# pcb.net
KiCad netlist of a schematic drawn in EasyEDA
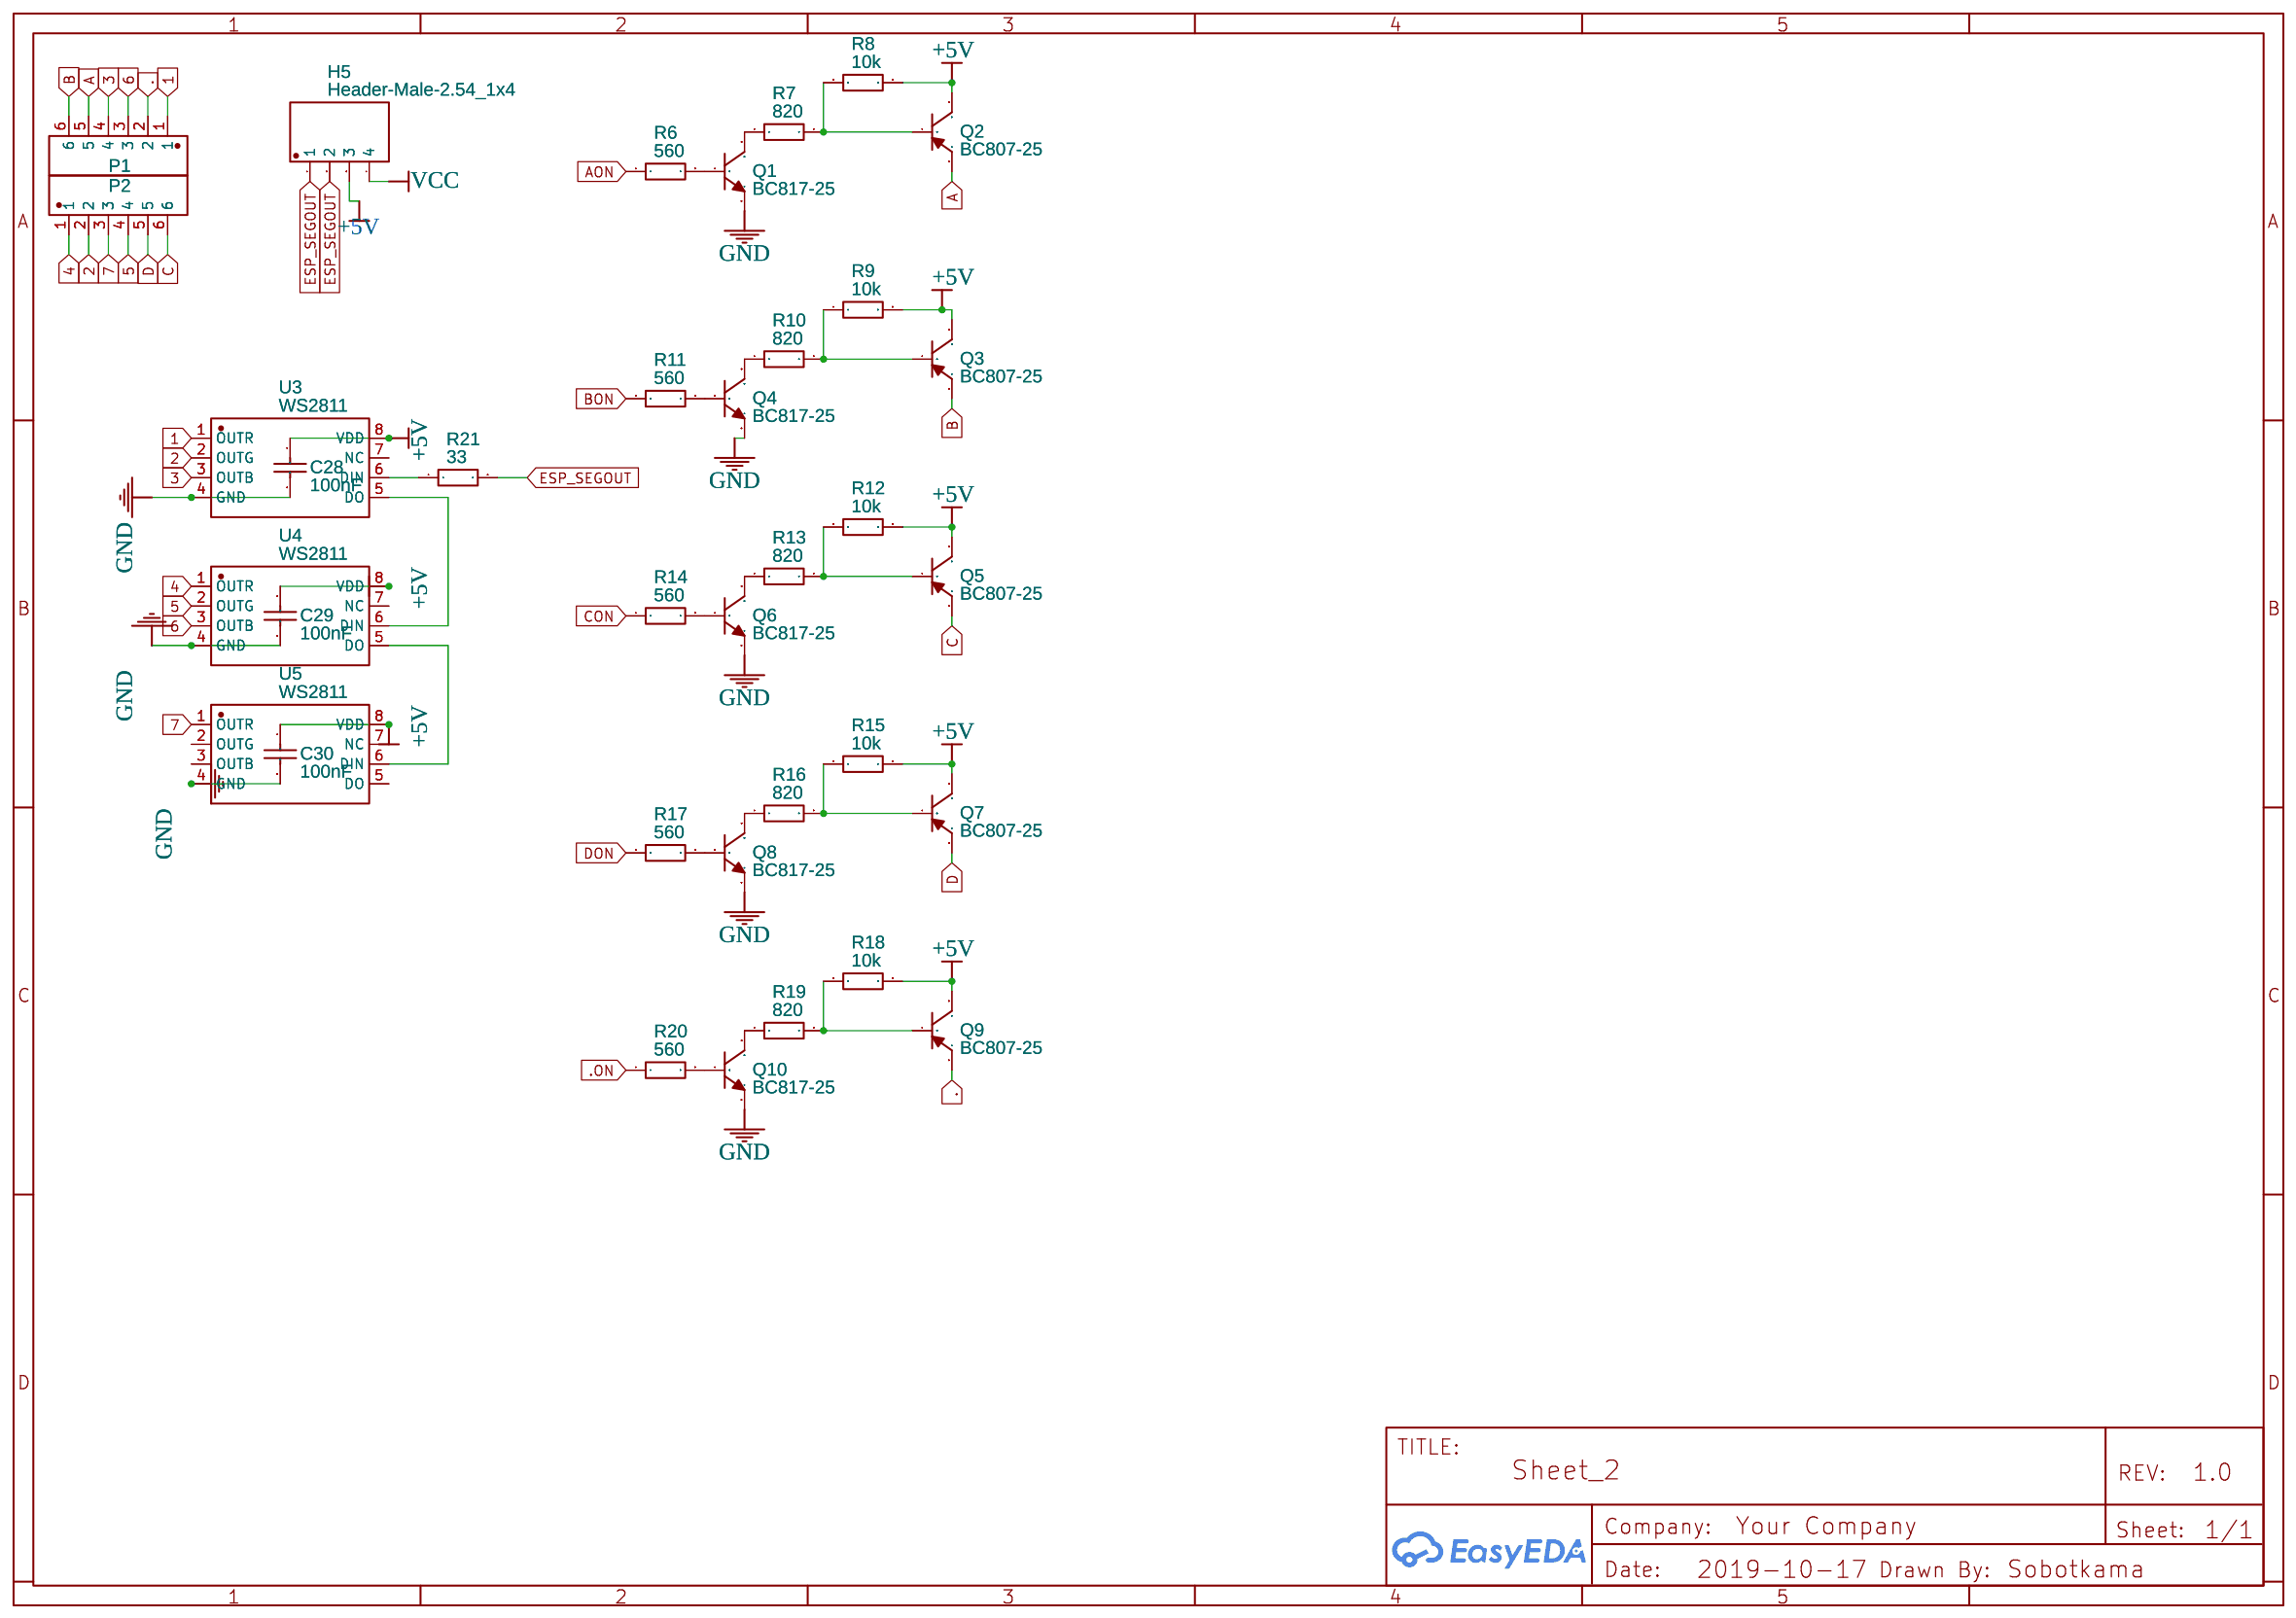
[diagram p0: Sheet_2]
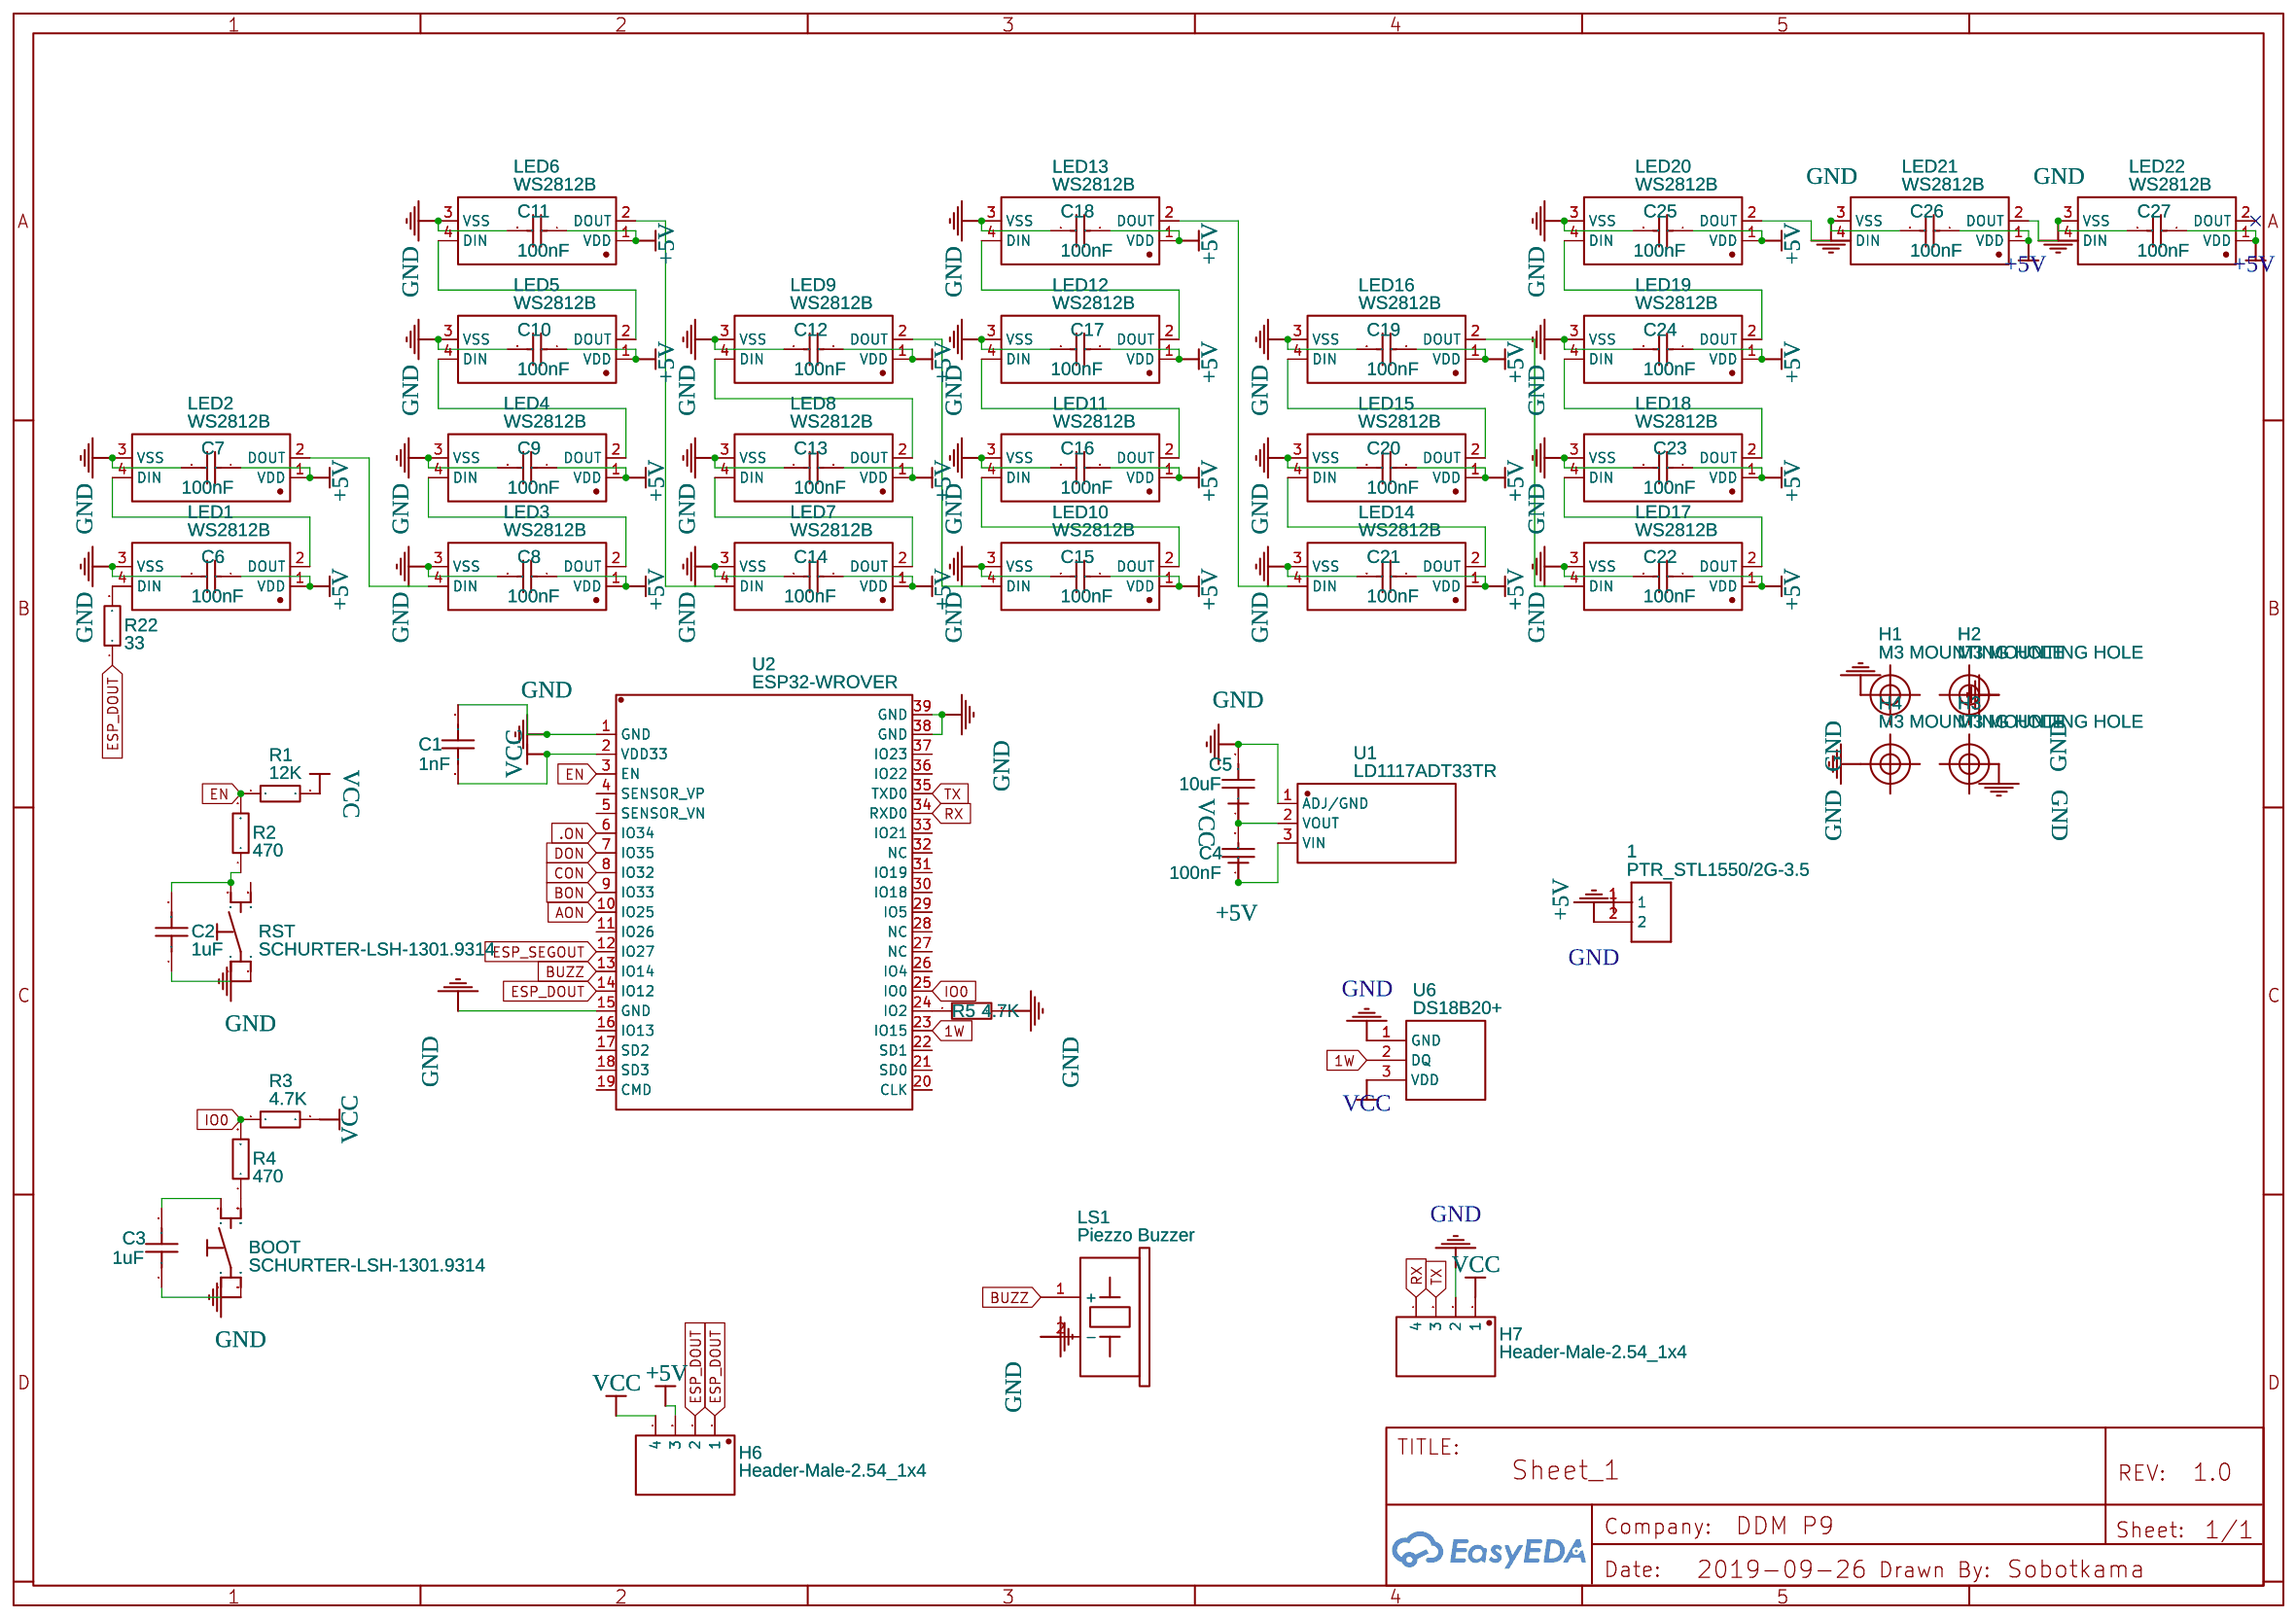
[diagram p1: Sheet_1]
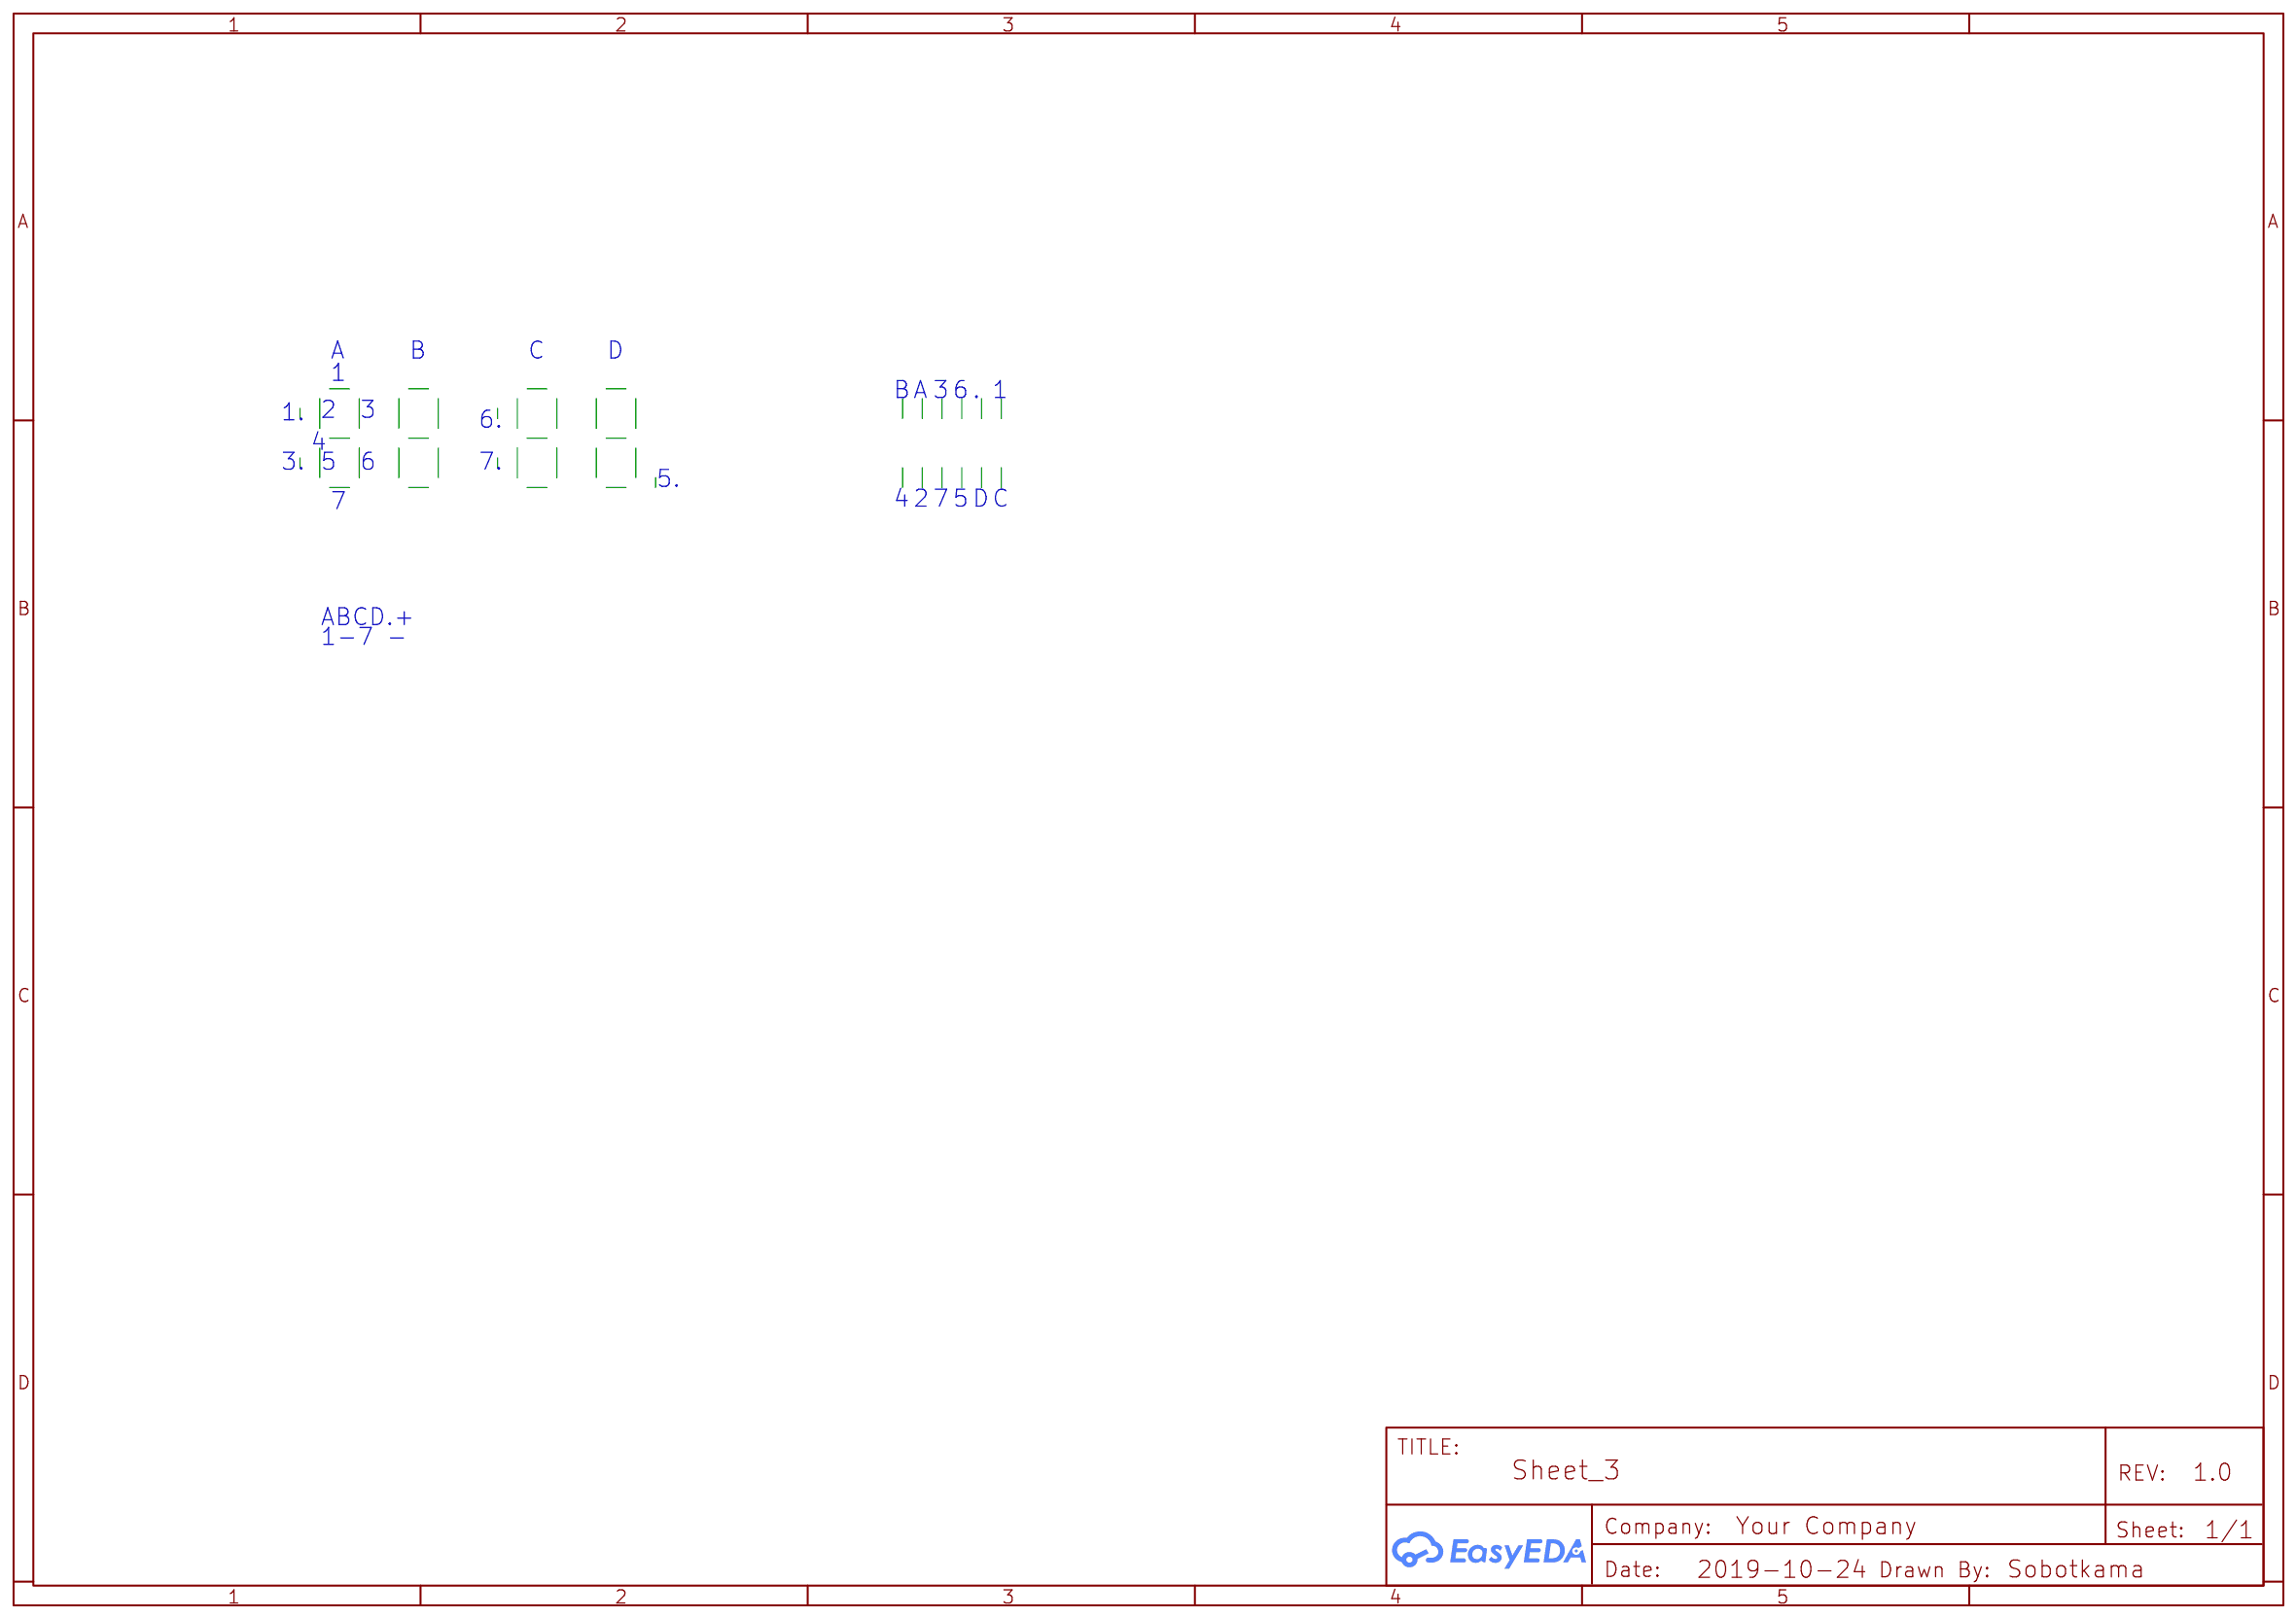
[diagram p2: DISPLAY_MAP]

(export (version "E")
  (design (tool "Eeschema 10.0.6"))
  (components
    (comp (ref "C28")
      (value "100nF")
      (fields
        (field (name "BOM_Manufacturer Part") "CL31B104KCFNNNE")
        (field (name "BOM_Supplier Part") "C1945")
      )
      (libsource (lib "") (part "CL31B104KCFNNNE"))
    )
    (comp (ref "C29")
      (value "100nF")
      (fields
        (field (name "BOM_Manufacturer Part") "CL31B104KCFNNNE")
        (field (name "BOM_Supplier Part") "C1945")
      )
      (libsource (lib "") (part "CL31B104KCFNNNE"))
    )
    (comp (ref "C30")
      (value "100nF")
      (fields
        (field (name "BOM_Manufacturer Part") "CL31B104KCFNNNE")
        (field (name "BOM_Supplier Part") "C1945")
      )
      (libsource (lib "") (part "CL31B104KCFNNNE"))
    )
    (comp (ref "H5")
      (value "Header-Male-2.54_1x4")
      (fields
        (field (name "BOM_Manufacturer Part") "210S-1*4P L=11.6MMGold-plated black")
        (field (name "BOM_Supplier Part") "C124378")
      )
      (libsource (lib "") (part "Header-Male-2.54_1x4"))
    )
    (comp (ref "P1")
      (value "Header-Female-2.54_1x6")
      (fields
        (field (name "BOM_Manufacturer Part") "Female header 1*6p")
        (field (name "BOM_Supplier Part") "C40877")
      )
      (libsource (lib "") (part "Unknown_53_72"))
    )
    (comp (ref "P2")
      (value "Header-Female-2.54_1x6")
      (fields
        (field (name "BOM_Manufacturer Part") "Female header 1*6p")
        (field (name "BOM_Supplier Part") "C40877")
      )
      (libsource (lib "") (part "Unknown_53_92"))
    )
    (comp (ref "Q1")
      (value "BC817-25")
      (fields (field (name "BOM_Supplier Part") "C8588"))
      (libsource (lib "") (part "Unknown_360_80"))
    )
    (comp (ref "Q2")
      (value "BC807-25")
      (fields (field (name "BOM_Supplier Part") "C181150"))
      (libsource (lib "") (part "Unknown_465_60"))
    )
    (comp (ref "Q3")
      (value "BC807-25")
      (fields (field (name "BOM_Supplier Part") "C181150"))
      (libsource (lib "") (part "Unknown_465_175"))
    )
    (comp (ref "Q4")
      (value "BC817-25")
      (fields (field (name "BOM_Supplier Part") "C8588"))
      (libsource (lib "") (part "Unknown_360_195"))
    )
    (comp (ref "Q5")
      (value "BC807-25")
      (fields (field (name "BOM_Supplier Part") "C181150"))
      (libsource (lib "") (part "Unknown_465_285"))
    )
    (comp (ref "Q6")
      (value "BC817-25")
      (fields (field (name "BOM_Supplier Part") "C8588"))
      (libsource (lib "") (part "Unknown_360_305"))
    )
    (comp (ref "Q7")
      (value "BC807-25")
      (fields (field (name "BOM_Supplier Part") "C181150"))
      (libsource (lib "") (part "Unknown_465_405"))
    )
    (comp (ref "Q8")
      (value "BC817-25")
      (fields (field (name "BOM_Supplier Part") "C8588"))
      (libsource (lib "") (part "Unknown_360_425"))
    )
    (comp (ref "Q9")
      (value "BC807-25")
      (fields (field (name "BOM_Supplier Part") "C181150"))
      (libsource (lib "") (part "Unknown_465_515"))
    )
    (comp (ref "Q10")
      (value "BC817-25")
      (fields (field (name "BOM_Supplier Part") "C8588"))
      (libsource (lib "") (part "Unknown_360_535"))
    )
    (comp (ref "R6")
      (value "560")
      (fields
        (field (name "BOM_Manufacturer Part") "RMC12065601%N")
        (field (name "BOM_Supplier Part") "C269625")
      )
      (libsource (lib "") (part "RMC12065601%N"))
    )
    (comp (ref "R7")
      (value "820")
      (fields
        (field (name "BOM_Manufacturer Part") "RC1206JR-071KL")
        (field (name "BOM_Supplier Part") "C112223")
      )
      (libsource (lib "") (part "RC1206JR-071KL"))
    )
    (comp (ref "R8")
      (value "10k")
      (fields
        (field (name "BOM_Manufacturer Part") "AECR1206F4K70K9")
        (field (name "BOM_Supplier Part") "C352065")
      )
      (libsource (lib "") (part "AECR1206F4K70K9"))
    )
    (comp (ref "R9")
      (value "10k")
      (fields
        (field (name "BOM_Manufacturer Part") "AECR1206F4K70K9")
        (field (name "BOM_Supplier Part") "C352065")
      )
      (libsource (lib "") (part "AECR1206F4K70K9"))
    )
    (comp (ref "R10")
      (value "820")
      (fields
        (field (name "BOM_Manufacturer Part") "RC1206JR-071KL")
        (field (name "BOM_Supplier Part") "C112223")
      )
      (libsource (lib "") (part "RC1206JR-071KL"))
    )
    (comp (ref "R11")
      (value "560")
      (fields
        (field (name "BOM_Manufacturer Part") "RMC12065601%N")
        (field (name "BOM_Supplier Part") "C269625")
      )
      (libsource (lib "") (part "RMC12065601%N"))
    )
    (comp (ref "R12")
      (value "10k")
      (fields
        (field (name "BOM_Manufacturer Part") "AECR1206F4K70K9")
        (field (name "BOM_Supplier Part") "C352065")
      )
      (libsource (lib "") (part "AECR1206F4K70K9"))
    )
    (comp (ref "R13")
      (value "820")
      (fields
        (field (name "BOM_Manufacturer Part") "RC1206JR-071KL")
        (field (name "BOM_Supplier Part") "C112223")
      )
      (libsource (lib "") (part "RC1206JR-071KL"))
    )
    (comp (ref "R14")
      (value "560")
      (fields
        (field (name "BOM_Manufacturer Part") "RMC12065601%N")
        (field (name "BOM_Supplier Part") "C269625")
      )
      (libsource (lib "") (part "RMC12065601%N"))
    )
    (comp (ref "R15")
      (value "10k")
      (fields
        (field (name "BOM_Manufacturer Part") "AECR1206F4K70K9")
        (field (name "BOM_Supplier Part") "C352065")
      )
      (libsource (lib "") (part "AECR1206F4K70K9"))
    )
    (comp (ref "R16")
      (value "820")
      (fields
        (field (name "BOM_Manufacturer Part") "RC1206JR-071KL")
        (field (name "BOM_Supplier Part") "C112223")
      )
      (libsource (lib "") (part "RC1206JR-071KL"))
    )
    (comp (ref "R17")
      (value "560")
      (fields
        (field (name "BOM_Manufacturer Part") "RMC12065601%N")
        (field (name "BOM_Supplier Part") "C269625")
      )
      (libsource (lib "") (part "RMC12065601%N"))
    )
    (comp (ref "R18")
      (value "10k")
      (fields
        (field (name "BOM_Manufacturer Part") "AECR1206F4K70K9")
        (field (name "BOM_Supplier Part") "C352065")
      )
      (libsource (lib "") (part "AECR1206F4K70K9"))
    )
    (comp (ref "R19")
      (value "820")
      (fields
        (field (name "BOM_Manufacturer Part") "RC1206JR-071KL")
        (field (name "BOM_Supplier Part") "C112223")
      )
      (libsource (lib "") (part "RC1206JR-071KL"))
    )
    (comp (ref "R20")
      (value "560")
      (fields
        (field (name "BOM_Manufacturer Part") "RMC12065601%N")
        (field (name "BOM_Supplier Part") "C269625")
      )
      (libsource (lib "") (part "RMC12065601%N"))
    )
    (comp (ref "R21")
      (value "33")
      (fields
        (field (name "BOM_Manufacturer Part") "RT1206FRD0720RL")
        (field (name "BOM_Supplier Part") "C136871")
      )
      (libsource (lib "") (part "RT1206FRD0720RL"))
    )
    (comp (ref "U3")
      (value "WS2811")
      (fields (field (name "BOM_Supplier Part") "C114581"))
      (libsource (lib "") (part "Unknown_140_230"))
    )
    (comp (ref "U4")
      (value "WS2811")
      (fields (field (name "BOM_Supplier Part") "C114581"))
      (libsource (lib "") (part "Unknown_140_305"))
    )
    (comp (ref "U5")
      (value "WS2811")
      (fields (field (name "BOM_Supplier Part") "C114581"))
      (libsource (lib "") (part "Unknown_140_375"))
    )
    (comp (ref "1") (value "PTR_STL1550/2G-3.5") (libsource (lib "") (part "Unknown_820_455")))
    (comp (ref "BOOT") (value "SCHURTER-LSH-1301.9314") (libsource (lib "") (part "Unknown_110_625")))
    (comp (ref "C1")
      (value "1nF")
      (fields
        (field (name "BOM_Manufacturer Part") "TCC1206X7R102K251DT")
        (field (name "BOM_Supplier Part") "C282816")
      )
      (libsource (lib "") (part "TCC1206X7R102K251DT"))
    )
    (comp (ref "C2")
      (value "1uF")
      (fields
        (field (name "BOM_Manufacturer Part") "GCM31MR71H105KA55L")
        (field (name "BOM_Supplier Part") "C85867")
      )
      (libsource (lib "") (part "GCM31MR71H105KA55L"))
    )
    (comp (ref "C3")
      (value "1uF")
      (fields
        (field (name "BOM_Manufacturer Part") "GCM31MR71H105KA55L")
        (field (name "BOM_Supplier Part") "C85867")
      )
      (libsource (lib "") (part "GCM31MR71H105KA55L"))
    )
    (comp (ref "C4")
      (value "100nF")
      (fields
        (field (name "BOM_Manufacturer Part") "C1206U104J050T")
        (field (name "BOM_Supplier Part") "C158070")
      )
      (libsource (lib "") (part "C1206U104J050T"))
    )
    (comp (ref "C5")
      (value "10uF")
      (fields
        (field (name "BOM_Manufacturer Part") "1206X106K160")
        (field (name "BOM_Supplier Part") "C105210")
      )
      (libsource (lib "") (part "1206X106K160"))
    )
    (comp (ref "C6")
      (value "100nF")
      (fields
        (field (name "BOM_Manufacturer Part") "CL31B104KCFNNNE")
        (field (name "BOM_Supplier Part") "C1945")
      )
      (libsource (lib "") (part "CL31B104KCFNNNE"))
    )
    (comp (ref "C7")
      (value "100nF")
      (fields
        (field (name "BOM_Manufacturer Part") "CL31B104KCFNNNE")
        (field (name "BOM_Supplier Part") "C1945")
      )
      (libsource (lib "") (part "CL31B104KCFNNNE"))
    )
    (comp (ref "C8")
      (value "100nF")
      (fields
        (field (name "BOM_Manufacturer Part") "CL31B104KCFNNNE")
        (field (name "BOM_Supplier Part") "C1945")
      )
      (libsource (lib "") (part "CL31B104KCFNNNE"))
    )
    (comp (ref "C9")
      (value "100nF")
      (fields
        (field (name "BOM_Manufacturer Part") "CL31B104KCFNNNE")
        (field (name "BOM_Supplier Part") "C1945")
      )
      (libsource (lib "") (part "CL31B104KCFNNNE"))
    )
    (comp (ref "C10")
      (value "100nF")
      (fields
        (field (name "BOM_Manufacturer Part") "CL31B104KCFNNNE")
        (field (name "BOM_Supplier Part") "C1945")
      )
      (libsource (lib "") (part "CL31B104KCFNNNE"))
    )
    (comp (ref "C11")
      (value "100nF")
      (fields
        (field (name "BOM_Manufacturer Part") "CL31B104KCFNNNE")
        (field (name "BOM_Supplier Part") "C1945")
      )
      (libsource (lib "") (part "CL31B104KCFNNNE"))
    )
    (comp (ref "C12")
      (value "100nF")
      (fields
        (field (name "BOM_Manufacturer Part") "CL31B104KCFNNNE")
        (field (name "BOM_Supplier Part") "C1945")
      )
      (libsource (lib "") (part "CL31B104KCFNNNE"))
    )
    (comp (ref "C13")
      (value "100nF")
      (fields
        (field (name "BOM_Manufacturer Part") "CL31B104KCFNNNE")
        (field (name "BOM_Supplier Part") "C1945")
      )
      (libsource (lib "") (part "CL31B104KCFNNNE"))
    )
    (comp (ref "C14")
      (value "100nF")
      (fields
        (field (name "BOM_Manufacturer Part") "CL31B104KCFNNNE")
        (field (name "BOM_Supplier Part") "C1945")
      )
      (libsource (lib "") (part "CL31B104KCFNNNE"))
    )
    (comp (ref "C15")
      (value "100nF")
      (fields
        (field (name "BOM_Manufacturer Part") "CL31B104KCFNNNE")
        (field (name "BOM_Supplier Part") "C1945")
      )
      (libsource (lib "") (part "CL31B104KCFNNNE"))
    )
    (comp (ref "C16")
      (value "100nF")
      (fields
        (field (name "BOM_Manufacturer Part") "CL31B104KCFNNNE")
        (field (name "BOM_Supplier Part") "C1945")
      )
      (libsource (lib "") (part "CL31B104KCFNNNE"))
    )
    (comp (ref "C17")
      (value "100nF")
      (fields
        (field (name "BOM_Manufacturer Part") "CL31B104KCFNNNE")
        (field (name "BOM_Supplier Part") "C1945")
      )
      (libsource (lib "") (part "CL31B104KCFNNNE"))
    )
    (comp (ref "C18")
      (value "100nF")
      (fields
        (field (name "BOM_Manufacturer Part") "CL31B104KCFNNNE")
        (field (name "BOM_Supplier Part") "C1945")
      )
      (libsource (lib "") (part "CL31B104KCFNNNE"))
    )
    (comp (ref "C19")
      (value "100nF")
      (fields
        (field (name "BOM_Manufacturer Part") "CL31B104KCFNNNE")
        (field (name "BOM_Supplier Part") "C1945")
      )
      (libsource (lib "") (part "CL31B104KCFNNNE"))
    )
    (comp (ref "C20")
      (value "100nF")
      (fields
        (field (name "BOM_Manufacturer Part") "CL31B104KCFNNNE")
        (field (name "BOM_Supplier Part") "C1945")
      )
      (libsource (lib "") (part "CL31B104KCFNNNE"))
    )
    (comp (ref "C21")
      (value "100nF")
      (fields
        (field (name "BOM_Manufacturer Part") "CL31B104KCFNNNE")
        (field (name "BOM_Supplier Part") "C1945")
      )
      (libsource (lib "") (part "CL31B104KCFNNNE"))
    )
    (comp (ref "C22")
      (value "100nF")
      (fields
        (field (name "BOM_Manufacturer Part") "CL31B104KCFNNNE")
        (field (name "BOM_Supplier Part") "C1945")
      )
      (libsource (lib "") (part "CL31B104KCFNNNE"))
    )
    (comp (ref "C23")
      (value "100nF")
      (fields
        (field (name "BOM_Manufacturer Part") "CL31B104KCFNNNE")
        (field (name "BOM_Supplier Part") "C1945")
      )
      (libsource (lib "") (part "CL31B104KCFNNNE"))
    )
    (comp (ref "C24")
      (value "100nF")
      (fields
        (field (name "BOM_Manufacturer Part") "CL31B104KCFNNNE")
        (field (name "BOM_Supplier Part") "C1945")
      )
      (libsource (lib "") (part "CL31B104KCFNNNE"))
    )
    (comp (ref "C25")
      (value "100nF")
      (fields
        (field (name "BOM_Manufacturer Part") "CL31B104KCFNNNE")
        (field (name "BOM_Supplier Part") "C1945")
      )
      (libsource (lib "") (part "CL31B104KCFNNNE"))
    )
    (comp (ref "C26")
      (value "100nF")
      (fields
        (field (name "BOM_Manufacturer Part") "CL31B104KCFNNNE")
        (field (name "BOM_Supplier Part") "C1945")
      )
      (libsource (lib "") (part "CL31B104KCFNNNE"))
    )
    (comp (ref "C27")
      (value "100nF")
      (fields
        (field (name "BOM_Manufacturer Part") "CL31B104KCFNNNE")
        (field (name "BOM_Supplier Part") "C1945")
      )
      (libsource (lib "") (part "CL31B104KCFNNNE"))
    )
    (comp (ref "H1")
      (value "M3 MOUNTING HOLE")
      (fields (field (name "BOM_Manufacturer Part") "M3 Mounting Hole"))
      (libsource (lib "") (part "Unknown_950_345"))
    )
    (comp (ref "H2")
      (value "M3 MOUNTING HOLE")
      (fields (field (name "BOM_Manufacturer Part") "M3 Mounting Hole"))
      (libsource (lib "") (part "Unknown_990_345"))
    )
    (comp (ref "H3")
      (value "M3 MOUNTING HOLE")
      (fields (field (name "BOM_Manufacturer Part") "M3 Mounting Hole"))
      (libsource (lib "") (part "Unknown_990_380"))
    )
    (comp (ref "H4")
      (value "M3 MOUNTING HOLE")
      (fields (field (name "BOM_Manufacturer Part") "M3 Mounting Hole"))
      (libsource (lib "") (part "Unknown_950_380"))
    )
    (comp (ref "H6")
      (value "Header-Male-2.54_1x4")
      (fields
        (field (name "BOM_Manufacturer Part") "210S-1*4P L=11.6MMGold-plated black")
        (field (name "BOM_Supplier Part") "C124378")
      )
      (libsource (lib "") (part "Header-Male-2.54_1x4"))
    )
    (comp (ref "H7")
      (value "Header-Male-2.54_1x4")
      (fields
        (field (name "BOM_Manufacturer Part") "210S-1*4P L=11.6MMGold-plated black")
        (field (name "BOM_Supplier Part") "C124378")
      )
      (libsource (lib "") (part "Header-Male-2.54_1x4"))
    )
    (comp (ref "LED1")
      (value "WS2812B")
      (fields (field (name "BOM_Supplier Part") "C114585"))
      (libsource (lib "") (part "Unknown_100_300"))
    )
    (comp (ref "LED2")
      (value "WS2812B")
      (fields (field (name "BOM_Supplier Part") "C114585"))
      (libsource (lib "") (part "Unknown_100_245"))
    )
    (comp (ref "LED3")
      (value "WS2812B")
      (fields (field (name "BOM_Supplier Part") "C114585"))
      (libsource (lib "") (part "Unknown_260_300"))
    )
    (comp (ref "LED4")
      (value "WS2812B")
      (fields (field (name "BOM_Supplier Part") "C114585"))
      (libsource (lib "") (part "Unknown_260_245"))
    )
    (comp (ref "LED5")
      (value "WS2812B")
      (fields (field (name "BOM_Supplier Part") "C114585"))
      (libsource (lib "") (part "Unknown_265_185"))
    )
    (comp (ref "LED6")
      (value "WS2812B")
      (fields (field (name "BOM_Supplier Part") "C114585"))
      (libsource (lib "") (part "Unknown_265_125"))
    )
    (comp (ref "LED7")
      (value "WS2812B")
      (fields (field (name "BOM_Supplier Part") "C114585"))
      (libsource (lib "") (part "Unknown_405_300"))
    )
    (comp (ref "LED8")
      (value "WS2812B")
      (fields (field (name "BOM_Supplier Part") "C114585"))
      (libsource (lib "") (part "Unknown_405_245"))
    )
    (comp (ref "LED9")
      (value "WS2812B")
      (fields (field (name "BOM_Supplier Part") "C114585"))
      (libsource (lib "") (part "Unknown_405_185"))
    )
    (comp (ref "LED10")
      (value "WS2812B")
      (fields (field (name "BOM_Supplier Part") "C114585"))
      (libsource (lib "") (part "Unknown_540_300"))
    )
    (comp (ref "LED11")
      (value "WS2812B")
      (fields (field (name "BOM_Supplier Part") "C114585"))
      (libsource (lib "") (part "Unknown_540_245"))
    )
    (comp (ref "LED12")
      (value "WS2812B")
      (fields (field (name "BOM_Supplier Part") "C114585"))
      (libsource (lib "") (part "Unknown_540_185"))
    )
    (comp (ref "LED13")
      (value "WS2812B")
      (fields (field (name "BOM_Supplier Part") "C114585"))
      (libsource (lib "") (part "Unknown_540_125"))
    )
    (comp (ref "LED14")
      (value "WS2812B")
      (fields (field (name "BOM_Supplier Part") "C114585"))
      (libsource (lib "") (part "Unknown_695_300"))
    )
    (comp (ref "LED15")
      (value "WS2812B")
      (fields (field (name "BOM_Supplier Part") "C114585"))
      (libsource (lib "") (part "Unknown_695_245"))
    )
    (comp (ref "LED16")
      (value "WS2812B")
      (fields (field (name "BOM_Supplier Part") "C114585"))
      (libsource (lib "") (part "Unknown_695_185"))
    )
    (comp (ref "LED17")
      (value "WS2812B")
      (fields (field (name "BOM_Supplier Part") "C114585"))
      (libsource (lib "") (part "Unknown_835_300"))
    )
    (comp (ref "LED18")
      (value "WS2812B")
      (fields (field (name "BOM_Supplier Part") "C114585"))
      (libsource (lib "") (part "Unknown_835_245"))
    )
    (comp (ref "LED19")
      (value "WS2812B")
      (fields (field (name "BOM_Supplier Part") "C114585"))
      (libsource (lib "") (part "Unknown_835_185"))
    )
    (comp (ref "LED20")
      (value "WS2812B")
      (fields (field (name "BOM_Supplier Part") "C114585"))
      (libsource (lib "") (part "Unknown_835_125"))
    )
    (comp (ref "LED21")
      (value "WS2812B")
      (fields (field (name "BOM_Supplier Part") "C114585"))
      (libsource (lib "") (part "Unknown_970_125"))
    )
    (comp (ref "LED22")
      (value "WS2812B")
      (fields (field (name "BOM_Supplier Part") "C114585"))
      (libsource (lib "") (part "Unknown_1085_125"))
    )
    (comp (ref "LS1") (value "Piezzo Buzzer") (libsource (lib "") (part "Unknown_520_625")))
    (comp (ref "R1")
      (value "12K")
      (fields
        (field (name "BOM_Manufacturer Part") "AC1206FR-0712KL")
        (field (name "BOM_Supplier Part") "C229302")
      )
      (libsource (lib "") (part "AC1206FR-0712KL"))
    )
    (comp (ref "R2")
      (value "470")
      (fields
        (field (name "BOM_Manufacturer Part") "AECR1206F470RK9")
        (field (name "BOM_Supplier Part") "C352069")
      )
      (libsource (lib "") (part "AECR1206F470RK9"))
    )
    (comp (ref "R3")
      (value "4.7K")
      (fields
        (field (name "BOM_Manufacturer Part") "CRCW12064K70FKEA")
        (field (name "BOM_Supplier Part") "C242482")
      )
      (libsource (lib "") (part "CRCW12064K70FKEA"))
    )
    (comp (ref "R4")
      (value "470")
      (fields
        (field (name "BOM_Manufacturer Part") "AECR1206F470RK9")
        (field (name "BOM_Supplier Part") "C352069")
      )
      (libsource (lib "") (part "AECR1206F470RK9"))
    )
    (comp (ref "R5")
      (value "4.7K")
      (fields
        (field (name "BOM_Manufacturer Part") "CRCW12064K70FKEA")
        (field (name "BOM_Supplier Part") "C242482")
      )
      (libsource (lib "") (part "CRCW12064K70FKEA"))
    )
    (comp (ref "R22")
      (value "33")
      (fields
        (field (name "BOM_Manufacturer Part") "RT1206FRD0720RL")
        (field (name "BOM_Supplier Part") "C136871")
      )
      (libsource (lib "") (part "RT1206FRD0720RL"))
    )
    (comp (ref "RST") (value "SCHURTER-LSH-1301.9314") (libsource (lib "") (part "Unknown_115_465")))
    (comp (ref "U1")
      (value "LD1117ADT33TR")
      (fields (field (name "BOM_Supplier Part") "C157401"))
      (libsource (lib "") (part "Unknown_690_410"))
    )
    (comp (ref "U2")
      (value "ESP32-WROVER")
      (fields (field (name "BOM_Supplier Part") "C129145"))
      (libsource (lib "") (part "Unknown_385_455"))
    )
    (comp (ref "U6")
      (value "DS18B20+")
      (fields (field (name "BOM_Supplier Part") "C9753"))
      (libsource (lib "") (part "Unknown_715_530"))
    )
  )
  (nets
    (net (code "1") (name "+5V") (class "Default")
      (node (ref "1") (pin "1") (pinfunction "1_1") (pintype "bidirectional"))
      (node (ref "C10") (pin "1") (pinfunction "1_1") (pintype "input"))
      (node (ref "C11") (pin "1") (pinfunction "1_1") (pintype "input"))
      (node (ref "C12") (pin "1") (pinfunction "1_1") (pintype "input"))
      (node (ref "C13") (pin "1") (pinfunction "1_1") (pintype "input"))
      (node (ref "C14") (pin "1") (pinfunction "1_1") (pintype "input"))
      (node (ref "C15") (pin "1") (pinfunction "1_1") (pintype "input"))
      (node (ref "C16") (pin "1") (pinfunction "1_1") (pintype "input"))
      (node (ref "C17") (pin "1") (pinfunction "1_1") (pintype "input"))
      (node (ref "C18") (pin "1") (pinfunction "1_1") (pintype "input"))
      (node (ref "C19") (pin "1") (pinfunction "1_1") (pintype "input"))
      (node (ref "C20") (pin "1") (pinfunction "1_1") (pintype "input"))
      (node (ref "C21") (pin "1") (pinfunction "1_1") (pintype "input"))
      (node (ref "C22") (pin "1") (pinfunction "1_1") (pintype "input"))
      (node (ref "C23") (pin "1") (pinfunction "1_1") (pintype "input"))
      (node (ref "C24") (pin "1") (pinfunction "1_1") (pintype "input"))
      (node (ref "C25") (pin "1") (pinfunction "1_1") (pintype "input"))
      (node (ref "C26") (pin "1") (pinfunction "1_1") (pintype "input"))
      (node (ref "C27") (pin "1") (pinfunction "1_1") (pintype "input"))
      (node (ref "C28") (pin "1") (pinfunction "1_1") (pintype "input"))
      (node (ref "C29") (pin "1") (pinfunction "1_1") (pintype "input"))
      (node (ref "C30") (pin "1") (pinfunction "1_1") (pintype "input"))
      (node (ref "C4") (pin "1") (pinfunction "1_1") (pintype "input"))
      (node (ref "C6") (pin "1") (pinfunction "1_1") (pintype "input"))
      (node (ref "C7") (pin "1") (pinfunction "1_1") (pintype "input"))
      (node (ref "C8") (pin "1") (pinfunction "1_1") (pintype "input"))
      (node (ref "C9") (pin "1") (pinfunction "1_1") (pintype "input"))
      (node (ref "H5") (pin "3") (pinfunction "3_3") (pintype "unspecified"))
      (node (ref "H6") (pin "3") (pinfunction "3_3") (pintype "unspecified"))
      (node (ref "LED1") (pin "1") (pinfunction "VDD_1") (pintype "unspecified"))
      (node (ref "LED10") (pin "1") (pinfunction "VDD_1") (pintype "unspecified"))
      (node (ref "LED11") (pin "1") (pinfunction "VDD_1") (pintype "unspecified"))
      (node (ref "LED12") (pin "1") (pinfunction "VDD_1") (pintype "unspecified"))
      (node (ref "LED13") (pin "1") (pinfunction "VDD_1") (pintype "unspecified"))
      (node (ref "LED14") (pin "1") (pinfunction "VDD_1") (pintype "unspecified"))
      (node (ref "LED15") (pin "1") (pinfunction "VDD_1") (pintype "unspecified"))
      (node (ref "LED16") (pin "1") (pinfunction "VDD_1") (pintype "unspecified"))
      (node (ref "LED17") (pin "1") (pinfunction "VDD_1") (pintype "unspecified"))
      (node (ref "LED18") (pin "1") (pinfunction "VDD_1") (pintype "unspecified"))
      (node (ref "LED19") (pin "1") (pinfunction "VDD_1") (pintype "unspecified"))
      (node (ref "LED2") (pin "1") (pinfunction "VDD_1") (pintype "unspecified"))
      (node (ref "LED20") (pin "1") (pinfunction "VDD_1") (pintype "unspecified"))
      (node (ref "LED21") (pin "1") (pinfunction "VDD_1") (pintype "unspecified"))
      (node (ref "LED22") (pin "1") (pinfunction "VDD_1") (pintype "unspecified"))
      (node (ref "LED3") (pin "1") (pinfunction "VDD_1") (pintype "unspecified"))
      (node (ref "LED4") (pin "1") (pinfunction "VDD_1") (pintype "unspecified"))
      (node (ref "LED5") (pin "1") (pinfunction "VDD_1") (pintype "unspecified"))
      (node (ref "LED6") (pin "1") (pinfunction "VDD_1") (pintype "unspecified"))
      (node (ref "LED7") (pin "1") (pinfunction "VDD_1") (pintype "unspecified"))
      (node (ref "LED8") (pin "1") (pinfunction "VDD_1") (pintype "unspecified"))
      (node (ref "LED9") (pin "1") (pinfunction "VDD_1") (pintype "unspecified"))
      (node (ref "Q2") (pin "3") (pinfunction "C_3") (pintype "input"))
      (node (ref "Q3") (pin "3") (pinfunction "C_3") (pintype "input"))
      (node (ref "Q5") (pin "3") (pinfunction "C_3") (pintype "input"))
      (node (ref "Q7") (pin "3") (pinfunction "C_3") (pintype "input"))
      (node (ref "Q9") (pin "3") (pinfunction "C_3") (pintype "input"))
      (node (ref "R12") (pin "2") (pinfunction "2_2") (pintype "unspecified"))
      (node (ref "R15") (pin "2") (pinfunction "2_2") (pintype "unspecified"))
      (node (ref "R18") (pin "2") (pinfunction "2_2") (pintype "unspecified"))
      (node (ref "R8") (pin "2") (pinfunction "2_2") (pintype "unspecified"))
      (node (ref "R9") (pin "2") (pinfunction "2_2") (pintype "unspecified"))
      (node (ref "U1") (pin "3") (pinfunction "VIN_3") (pintype "unspecified"))
      (node (ref "U3") (pin "8") (pinfunction "VDD_8") (pintype "unspecified"))
      (node (ref "U4") (pin "8") (pinfunction "VDD_8") (pintype "unspecified"))
      (node (ref "U5") (pin "8") (pinfunction "VDD_8") (pintype "unspecified"))
    )
    (net (code "2") (name ".") (class "Default")
      (node (ref "P1") (pin "2") (pinfunction "2_2") (pintype "unspecified"))
      (node (ref "Q9") (pin "2") (pinfunction "E_2") (pintype "input"))
    )
    (net (code "3") (name ".ON") (class "Default")
      (node (ref "R20") (pin "1") (pinfunction "1_1") (pintype "unspecified"))
      (node (ref "U2") (pin "6") (pinfunction "IO34_6") (pintype "unspecified"))
    )
    (net (code "4") (name "1") (class "Default")
      (node (ref "P1") (pin "1") (pinfunction "1_1") (pintype "unspecified"))
      (node (ref "U3") (pin "1") (pinfunction "OUTR_1") (pintype "unspecified"))
    )
    (net (code "5") (name "1W") (class "Default")
      (node (ref "U2") (pin "23") (pinfunction "IO15_23") (pintype "unspecified"))
      (node (ref "U6") (pin "2") (pinfunction "DQ_2") (pintype "unspecified"))
    )
    (net (code "6") (name "2") (class "Default")
      (node (ref "P2") (pin "2") (pinfunction "2_2") (pintype "unspecified"))
      (node (ref "U3") (pin "2") (pinfunction "OUTG_2") (pintype "unspecified"))
    )
    (net (code "7") (name "3") (class "Default")
      (node (ref "P1") (pin "4") (pinfunction "4_4") (pintype "unspecified"))
      (node (ref "U3") (pin "3") (pinfunction "OUTB_3") (pintype "unspecified"))
    )
    (net (code "8") (name "4") (class "Default")
      (node (ref "P2") (pin "1") (pinfunction "1_1") (pintype "unspecified"))
      (node (ref "U4") (pin "1") (pinfunction "OUTR_1") (pintype "unspecified"))
    )
    (net (code "9") (name "5") (class "Default")
      (node (ref "P2") (pin "4") (pinfunction "4_4") (pintype "unspecified"))
      (node (ref "U4") (pin "2") (pinfunction "OUTG_2") (pintype "unspecified"))
    )
    (net (code "10") (name "6") (class "Default")
      (node (ref "P1") (pin "3") (pinfunction "3_3") (pintype "unspecified"))
      (node (ref "U4") (pin "3") (pinfunction "OUTB_3") (pintype "unspecified"))
    )
    (net (code "11") (name "7") (class "Default")
      (node (ref "P2") (pin "3") (pinfunction "3_3") (pintype "unspecified"))
      (node (ref "U5") (pin "1") (pinfunction "OUTR_1") (pintype "unspecified"))
    )
    (net (code "12") (name "A") (class "Default")
      (node (ref "P1") (pin "5") (pinfunction "5_5") (pintype "unspecified"))
      (node (ref "Q2") (pin "2") (pinfunction "E_2") (pintype "input"))
    )
    (net (code "13") (name "AON") (class "Default")
      (node (ref "R6") (pin "1") (pinfunction "1_1") (pintype "unspecified"))
      (node (ref "U2") (pin "10") (pinfunction "IO25_10") (pintype "unspecified"))
    )
    (net (code "14") (name "B") (class "Default")
      (node (ref "P1") (pin "6") (pinfunction "6_6") (pintype "unspecified"))
      (node (ref "Q3") (pin "2") (pinfunction "E_2") (pintype "input"))
    )
    (net (code "15") (name "BON") (class "Default")
      (node (ref "R11") (pin "1") (pinfunction "1_1") (pintype "unspecified"))
      (node (ref "U2") (pin "9") (pinfunction "IO33_9") (pintype "unspecified"))
    )
    (net (code "16") (name "BUZZ") (class "Default")
      (node (ref "LS1") (pin "1") (pinfunction "+_1") (pintype "unspecified"))
      (node (ref "U2") (pin "13") (pinfunction "IO14_13") (pintype "unspecified"))
    )
    (net (code "17") (name "C") (class "Default")
      (node (ref "P2") (pin "6") (pinfunction "6_6") (pintype "unspecified"))
      (node (ref "Q5") (pin "2") (pinfunction "E_2") (pintype "input"))
    )
    (net (code "18") (name "CON") (class "Default")
      (node (ref "R14") (pin "1") (pinfunction "1_1") (pintype "unspecified"))
      (node (ref "U2") (pin "8") (pinfunction "IO32_8") (pintype "unspecified"))
    )
    (net (code "19") (name "D") (class "Default")
      (node (ref "P2") (pin "5") (pinfunction "5_5") (pintype "unspecified"))
      (node (ref "Q7") (pin "2") (pinfunction "E_2") (pintype "input"))
    )
    (net (code "20") (name "DON") (class "Default")
      (node (ref "R17") (pin "1") (pinfunction "1_1") (pintype "unspecified"))
      (node (ref "U2") (pin "7") (pinfunction "IO35_7") (pintype "unspecified"))
    )
    (net (code "21") (name "EN") (class "Default")
      (node (ref "R1") (pin "1") (pinfunction "1_1") (pintype "unspecified"))
      (node (ref "R2") (pin "2") (pinfunction "2_2") (pintype "unspecified"))
      (node (ref "U2") (pin "3") (pinfunction "EN_3") (pintype "unspecified"))
    )
    (net (code "22") (name "ESP_DOUT") (class "Default")
      (node (ref "H6") (pin "1") (pinfunction "1_1") (pintype "unspecified"))
      (node (ref "H6") (pin "2") (pinfunction "2_2") (pintype "unspecified"))
      (node (ref "R22") (pin "1") (pinfunction "1_1") (pintype "unspecified"))
      (node (ref "U2") (pin "14") (pinfunction "IO12_14") (pintype "unspecified"))
    )
    (net (code "23") (name "ESP_SEGOUT") (class "Default")
      (node (ref "H5") (pin "1") (pinfunction "1_1") (pintype "unspecified"))
      (node (ref "H5") (pin "2") (pinfunction "2_2") (pintype "unspecified"))
      (node (ref "R21") (pin "2") (pinfunction "2_2") (pintype "unspecified"))
      (node (ref "U2") (pin "12") (pinfunction "IO27_12") (pintype "unspecified"))
    )
    (net (code "24") (name "GND") (class "Default")
      (node (ref "1") (pin "2") (pinfunction "2_2") (pintype "bidirectional"))
      (node (ref "BOOT") (pin "C2") (pinfunction "C_C2") (pintype "unspecified"))
      (node (ref "C1") (pin "2") (pinfunction "2_2") (pintype "unspecified"))
      (node (ref "C10") (pin "2") (pinfunction "2_2") (pintype "input"))
      (node (ref "C11") (pin "2") (pinfunction "2_2") (pintype "input"))
      (node (ref "C12") (pin "2") (pinfunction "2_2") (pintype "input"))
      (node (ref "C13") (pin "2") (pinfunction "2_2") (pintype "input"))
      (node (ref "C14") (pin "2") (pinfunction "2_2") (pintype "input"))
      (node (ref "C15") (pin "2") (pinfunction "2_2") (pintype "input"))
      (node (ref "C16") (pin "2") (pinfunction "2_2") (pintype "input"))
      (node (ref "C17") (pin "2") (pinfunction "2_2") (pintype "input"))
      (node (ref "C18") (pin "2") (pinfunction "2_2") (pintype "input"))
      (node (ref "C19") (pin "2") (pinfunction "2_2") (pintype "input"))
      (node (ref "C20") (pin "2") (pinfunction "2_2") (pintype "input"))
      (node (ref "C21") (pin "2") (pinfunction "2_2") (pintype "input"))
      (node (ref "C22") (pin "2") (pinfunction "2_2") (pintype "input"))
      (node (ref "C23") (pin "2") (pinfunction "2_2") (pintype "input"))
      (node (ref "C24") (pin "2") (pinfunction "2_2") (pintype "input"))
      (node (ref "C25") (pin "2") (pinfunction "2_2") (pintype "input"))
      (node (ref "C26") (pin "2") (pinfunction "2_2") (pintype "input"))
      (node (ref "C27") (pin "2") (pinfunction "2_2") (pintype "input"))
      (node (ref "C28") (pin "2") (pinfunction "2_2") (pintype "input"))
      (node (ref "C29") (pin "2") (pinfunction "2_2") (pintype "input"))
      (node (ref "C30") (pin "2") (pinfunction "2_2") (pintype "input"))
      (node (ref "C5") (pin "2") (pinfunction "2_2") (pintype "unspecified"))
      (node (ref "C6") (pin "2") (pinfunction "2_2") (pintype "input"))
      (node (ref "C7") (pin "2") (pinfunction "2_2") (pintype "input"))
      (node (ref "C8") (pin "2") (pinfunction "2_2") (pintype "input"))
      (node (ref "C9") (pin "2") (pinfunction "2_2") (pintype "input"))
      (node (ref "H7") (pin "2") (pinfunction "2_2") (pintype "unspecified"))
      (node (ref "LED1") (pin "3") (pinfunction "VSS_3") (pintype "unspecified"))
      (node (ref "LED10") (pin "3") (pinfunction "VSS_3") (pintype "unspecified"))
      (node (ref "LED11") (pin "3") (pinfunction "VSS_3") (pintype "unspecified"))
      (node (ref "LED12") (pin "3") (pinfunction "VSS_3") (pintype "unspecified"))
      (node (ref "LED13") (pin "3") (pinfunction "VSS_3") (pintype "unspecified"))
      (node (ref "LED14") (pin "3") (pinfunction "VSS_3") (pintype "unspecified"))
      (node (ref "LED15") (pin "3") (pinfunction "VSS_3") (pintype "unspecified"))
      (node (ref "LED16") (pin "3") (pinfunction "VSS_3") (pintype "unspecified"))
      (node (ref "LED17") (pin "3") (pinfunction "VSS_3") (pintype "unspecified"))
      (node (ref "LED18") (pin "3") (pinfunction "VSS_3") (pintype "unspecified"))
      (node (ref "LED19") (pin "3") (pinfunction "VSS_3") (pintype "unspecified"))
      (node (ref "LED2") (pin "3") (pinfunction "VSS_3") (pintype "unspecified"))
      (node (ref "LED20") (pin "3") (pinfunction "VSS_3") (pintype "unspecified"))
      (node (ref "LED21") (pin "3") (pinfunction "VSS_3") (pintype "unspecified"))
      (node (ref "LED22") (pin "3") (pinfunction "VSS_3") (pintype "unspecified"))
      (node (ref "LED3") (pin "3") (pinfunction "VSS_3") (pintype "unspecified"))
      (node (ref "LED4") (pin "3") (pinfunction "VSS_3") (pintype "unspecified"))
      (node (ref "LED5") (pin "3") (pinfunction "VSS_3") (pintype "unspecified"))
      (node (ref "LED6") (pin "3") (pinfunction "VSS_3") (pintype "unspecified"))
      (node (ref "LED7") (pin "3") (pinfunction "VSS_3") (pintype "unspecified"))
      (node (ref "LED8") (pin "3") (pinfunction "VSS_3") (pintype "unspecified"))
      (node (ref "LED9") (pin "3") (pinfunction "VSS_3") (pintype "unspecified"))
      (node (ref "LS1") (pin "2") (pinfunction "-_2") (pintype "unspecified"))
      (node (ref "Q1") (pin "2") (pinfunction "E_2") (pintype "unspecified"))
      (node (ref "Q10") (pin "2") (pinfunction "E_2") (pintype "unspecified"))
      (node (ref "Q4") (pin "2") (pinfunction "E_2") (pintype "unspecified"))
      (node (ref "Q6") (pin "2") (pinfunction "E_2") (pintype "unspecified"))
      (node (ref "Q8") (pin "2") (pinfunction "E_2") (pintype "unspecified"))
      (node (ref "R5") (pin "2") (pinfunction "2_2") (pintype "unspecified"))
      (node (ref "RST") (pin "C2") (pinfunction "C_C2") (pintype "unspecified"))
      (node (ref "U1") (pin "1") (pinfunction "ADJ/GND_1") (pintype "unspecified"))
      (node (ref "U2") (pin "1") (pinfunction "GND_1") (pintype "unspecified"))
      (node (ref "U2") (pin "15") (pinfunction "GND_15") (pintype "unspecified"))
      (node (ref "U2") (pin "38") (pinfunction "GND_38") (pintype "unspecified"))
      (node (ref "U2") (pin "39") (pinfunction "GND_39") (pintype "unspecified"))
      (node (ref "U3") (pin "4") (pinfunction "GND_4") (pintype "unspecified"))
      (node (ref "U4") (pin "4") (pinfunction "GND_4") (pintype "unspecified"))
      (node (ref "U5") (pin "4") (pinfunction "GND_4") (pintype "unspecified"))
      (node (ref "U6") (pin "1") (pinfunction "GND_1") (pintype "unspecified"))
    )
    (net (code "25") (name "IO0") (class "Default")
      (node (ref "R3") (pin "1") (pinfunction "1_1") (pintype "unspecified"))
      (node (ref "R4") (pin "2") (pinfunction "2_2") (pintype "unspecified"))
      (node (ref "U2") (pin "25") (pinfunction "IO0_25") (pintype "unspecified"))
    )
    (net (code "26") (name "Net-(BOOT-C-PadC1)") (class "Default")
      (node (ref "BOOT") (pin "C1") (pinfunction "C_C1") (pintype "unspecified"))
      (node (ref "C3") (pin "1") (pinfunction "1_1") (pintype "unspecified"))
    )
    (net (code "27") (name "Net-(BOOT-NO-PadNO1)") (class "Default")
      (node (ref "BOOT") (pin "NO1") (pinfunction "NO_NO1") (pintype "unspecified"))
      (node (ref "C3") (pin "2") (pinfunction "2_2") (pintype "unspecified"))
    )
    (net (code "28") (name "Net-(BOOT-NO-PadNO2)") (class "Default")
      (node (ref "BOOT") (pin "NO2") (pinfunction "NO_NO2") (pintype "unspecified"))
      (node (ref "R4") (pin "1") (pinfunction "1_1") (pintype "unspecified"))
    )
    (net (code "29") (name "Net-(C2-Pad1)") (class "Default")
      (node (ref "C2") (pin "1") (pinfunction "1_1") (pintype "unspecified"))
      (node (ref "RST") (pin "C1") (pinfunction "C_C1") (pintype "unspecified"))
    )
    (net (code "30") (name "Net-(C2-Pad2)") (class "Default")
      (node (ref "C2") (pin "2") (pinfunction "2_2") (pintype "unspecified"))
      (node (ref "R2") (pin "1") (pinfunction "1_1") (pintype "unspecified"))
      (node (ref "RST") (pin "NO1") (pinfunction "NO_NO1") (pintype "unspecified"))
    )
    (net (code "31") (name "Net-(LED1-DIN)") (class "Default")
      (node (ref "LED1") (pin "4") (pinfunction "DIN_4") (pintype "unspecified"))
      (node (ref "R22") (pin "2") (pinfunction "2_2") (pintype "unspecified"))
    )
    (net (code "32") (name "Net-(LED1-DOUT)") (class "Default")
      (node (ref "LED1") (pin "2") (pinfunction "DOUT_2") (pintype "unspecified"))
      (node (ref "LED2") (pin "4") (pinfunction "DIN_4") (pintype "unspecified"))
    )
    (net (code "33") (name "Net-(LED2-DOUT)") (class "Default")
      (node (ref "LED2") (pin "2") (pinfunction "DOUT_2") (pintype "unspecified"))
      (node (ref "LED3") (pin "4") (pinfunction "DIN_4") (pintype "unspecified"))
    )
    (net (code "34") (name "Net-(LED3-DOUT)") (class "Default")
      (node (ref "LED3") (pin "2") (pinfunction "DOUT_2") (pintype "unspecified"))
      (node (ref "LED4") (pin "4") (pinfunction "DIN_4") (pintype "unspecified"))
    )
    (net (code "35") (name "Net-(LED4-DOUT)") (class "Default")
      (node (ref "LED4") (pin "2") (pinfunction "DOUT_2") (pintype "unspecified"))
      (node (ref "LED5") (pin "4") (pinfunction "DIN_4") (pintype "unspecified"))
    )
    (net (code "36") (name "Net-(LED5-DOUT)") (class "Default")
      (node (ref "LED5") (pin "2") (pinfunction "DOUT_2") (pintype "unspecified"))
      (node (ref "LED6") (pin "4") (pinfunction "DIN_4") (pintype "unspecified"))
    )
    (net (code "37") (name "Net-(LED6-DOUT)") (class "Default")
      (node (ref "LED6") (pin "2") (pinfunction "DOUT_2") (pintype "unspecified"))
      (node (ref "LED7") (pin "4") (pinfunction "DIN_4") (pintype "unspecified"))
    )
    (net (code "38") (name "Net-(LED7-DOUT)") (class "Default")
      (node (ref "LED7") (pin "2") (pinfunction "DOUT_2") (pintype "unspecified"))
      (node (ref "LED8") (pin "4") (pinfunction "DIN_4") (pintype "unspecified"))
    )
    (net (code "39") (name "Net-(LED8-DOUT)") (class "Default")
      (node (ref "LED8") (pin "2") (pinfunction "DOUT_2") (pintype "unspecified"))
      (node (ref "LED9") (pin "4") (pinfunction "DIN_4") (pintype "unspecified"))
    )
    (net (code "40") (name "Net-(LED10-DIN)") (class "Default")
      (node (ref "LED10") (pin "4") (pinfunction "DIN_4") (pintype "unspecified"))
      (node (ref "LED9") (pin "2") (pinfunction "DOUT_2") (pintype "unspecified"))
    )
    (net (code "41") (name "Net-(LED10-DOUT)") (class "Default")
      (node (ref "LED10") (pin "2") (pinfunction "DOUT_2") (pintype "unspecified"))
      (node (ref "LED11") (pin "4") (pinfunction "DIN_4") (pintype "unspecified"))
    )
    (net (code "42") (name "Net-(LED11-DOUT)") (class "Default")
      (node (ref "LED11") (pin "2") (pinfunction "DOUT_2") (pintype "unspecified"))
      (node (ref "LED12") (pin "4") (pinfunction "DIN_4") (pintype "unspecified"))
    )
    (net (code "43") (name "Net-(LED12-DOUT)") (class "Default")
      (node (ref "LED12") (pin "2") (pinfunction "DOUT_2") (pintype "unspecified"))
      (node (ref "LED13") (pin "4") (pinfunction "DIN_4") (pintype "unspecified"))
    )
    (net (code "44") (name "Net-(LED13-DOUT)") (class "Default")
      (node (ref "LED13") (pin "2") (pinfunction "DOUT_2") (pintype "unspecified"))
      (node (ref "LED14") (pin "4") (pinfunction "DIN_4") (pintype "unspecified"))
    )
    (net (code "45") (name "Net-(LED14-DOUT)") (class "Default")
      (node (ref "LED14") (pin "2") (pinfunction "DOUT_2") (pintype "unspecified"))
      (node (ref "LED15") (pin "4") (pinfunction "DIN_4") (pintype "unspecified"))
    )
    (net (code "46") (name "Net-(LED15-DOUT)") (class "Default")
      (node (ref "LED15") (pin "2") (pinfunction "DOUT_2") (pintype "unspecified"))
      (node (ref "LED16") (pin "4") (pinfunction "DIN_4") (pintype "unspecified"))
    )
    (net (code "47") (name "Net-(LED16-DOUT)") (class "Default")
      (node (ref "LED16") (pin "2") (pinfunction "DOUT_2") (pintype "unspecified"))
      (node (ref "LED17") (pin "4") (pinfunction "DIN_4") (pintype "unspecified"))
    )
    (net (code "48") (name "Net-(LED17-DOUT)") (class "Default")
      (node (ref "LED17") (pin "2") (pinfunction "DOUT_2") (pintype "unspecified"))
      (node (ref "LED18") (pin "4") (pinfunction "DIN_4") (pintype "unspecified"))
    )
    (net (code "49") (name "Net-(LED18-DOUT)") (class "Default")
      (node (ref "LED18") (pin "2") (pinfunction "DOUT_2") (pintype "unspecified"))
      (node (ref "LED19") (pin "4") (pinfunction "DIN_4") (pintype "unspecified"))
    )
    (net (code "50") (name "Net-(LED19-DOUT)") (class "Default")
      (node (ref "LED19") (pin "2") (pinfunction "DOUT_2") (pintype "unspecified"))
      (node (ref "LED20") (pin "4") (pinfunction "DIN_4") (pintype "unspecified"))
    )
    (net (code "51") (name "Net-(LED20-DOUT)") (class "Default")
      (node (ref "LED20") (pin "2") (pinfunction "DOUT_2") (pintype "unspecified"))
      (node (ref "LED21") (pin "4") (pinfunction "DIN_4") (pintype "unspecified"))
    )
    (net (code "52") (name "Net-(LED21-DOUT)") (class "Default")
      (node (ref "LED21") (pin "2") (pinfunction "DOUT_2") (pintype "unspecified"))
      (node (ref "LED22") (pin "4") (pinfunction "DIN_4") (pintype "unspecified"))
    )
    (net (code "53") (name "Net-(Q1-B)") (class "Default")
      (node (ref "Q1") (pin "1") (pinfunction "B_1") (pintype "unspecified"))
      (node (ref "R6") (pin "2") (pinfunction "2_2") (pintype "unspecified"))
    )
    (net (code "54") (name "Net-(Q1-C)") (class "Default")
      (node (ref "Q1") (pin "3") (pinfunction "C_3") (pintype "unspecified"))
      (node (ref "R7") (pin "1") (pinfunction "1_1") (pintype "input"))
    )
    (net (code "55") (name "Net-(Q2-B)") (class "Default")
      (node (ref "Q2") (pin "1") (pinfunction "B_1") (pintype "input"))
      (node (ref "R7") (pin "2") (pinfunction "2_2") (pintype "input"))
      (node (ref "R8") (pin "1") (pinfunction "1_1") (pintype "unspecified"))
    )
    (net (code "56") (name "Net-(Q3-B)") (class "Default")
      (node (ref "Q3") (pin "1") (pinfunction "B_1") (pintype "input"))
      (node (ref "R10") (pin "2") (pinfunction "2_2") (pintype "input"))
      (node (ref "R9") (pin "1") (pinfunction "1_1") (pintype "unspecified"))
    )
    (net (code "57") (name "Net-(Q4-B)") (class "Default")
      (node (ref "Q4") (pin "1") (pinfunction "B_1") (pintype "unspecified"))
      (node (ref "R11") (pin "2") (pinfunction "2_2") (pintype "unspecified"))
    )
    (net (code "58") (name "Net-(Q4-C)") (class "Default")
      (node (ref "Q4") (pin "3") (pinfunction "C_3") (pintype "unspecified"))
      (node (ref "R10") (pin "1") (pinfunction "1_1") (pintype "input"))
    )
    (net (code "59") (name "Net-(Q5-B)") (class "Default")
      (node (ref "Q5") (pin "1") (pinfunction "B_1") (pintype "input"))
      (node (ref "R12") (pin "1") (pinfunction "1_1") (pintype "unspecified"))
      (node (ref "R13") (pin "2") (pinfunction "2_2") (pintype "input"))
    )
    (net (code "60") (name "Net-(Q6-B)") (class "Default")
      (node (ref "Q6") (pin "1") (pinfunction "B_1") (pintype "unspecified"))
      (node (ref "R14") (pin "2") (pinfunction "2_2") (pintype "unspecified"))
    )
    (net (code "61") (name "Net-(Q6-C)") (class "Default")
      (node (ref "Q6") (pin "3") (pinfunction "C_3") (pintype "unspecified"))
      (node (ref "R13") (pin "1") (pinfunction "1_1") (pintype "input"))
    )
    (net (code "62") (name "Net-(Q7-B)") (class "Default")
      (node (ref "Q7") (pin "1") (pinfunction "B_1") (pintype "input"))
      (node (ref "R15") (pin "1") (pinfunction "1_1") (pintype "unspecified"))
      (node (ref "R16") (pin "2") (pinfunction "2_2") (pintype "input"))
    )
    (net (code "63") (name "Net-(Q8-B)") (class "Default")
      (node (ref "Q8") (pin "1") (pinfunction "B_1") (pintype "unspecified"))
      (node (ref "R17") (pin "2") (pinfunction "2_2") (pintype "unspecified"))
    )
    (net (code "64") (name "Net-(Q8-C)") (class "Default")
      (node (ref "Q8") (pin "3") (pinfunction "C_3") (pintype "unspecified"))
      (node (ref "R16") (pin "1") (pinfunction "1_1") (pintype "input"))
    )
    (net (code "65") (name "Net-(Q9-B)") (class "Default")
      (node (ref "Q9") (pin "1") (pinfunction "B_1") (pintype "input"))
      (node (ref "R18") (pin "1") (pinfunction "1_1") (pintype "unspecified"))
      (node (ref "R19") (pin "2") (pinfunction "2_2") (pintype "input"))
    )
    (net (code "66") (name "Net-(Q10-B)") (class "Default")
      (node (ref "Q10") (pin "1") (pinfunction "B_1") (pintype "unspecified"))
      (node (ref "R20") (pin "2") (pinfunction "2_2") (pintype "unspecified"))
    )
    (net (code "67") (name "Net-(Q10-C)") (class "Default")
      (node (ref "Q10") (pin "3") (pinfunction "C_3") (pintype "unspecified"))
      (node (ref "R19") (pin "1") (pinfunction "1_1") (pintype "input"))
    )
    (net (code "68") (name "Net-(U2-IO2)") (class "Default")
      (node (ref "R5") (pin "1") (pinfunction "1_1") (pintype "unspecified"))
      (node (ref "U2") (pin "24") (pinfunction "IO2_24") (pintype "unspecified"))
    )
    (net (code "69") (name "Net-(U3-DIN)") (class "Default")
      (node (ref "R21") (pin "1") (pinfunction "1_1") (pintype "unspecified"))
      (node (ref "U3") (pin "6") (pinfunction "DIN_6") (pintype "unspecified"))
    )
    (net (code "70") (name "Net-(U3-DO)") (class "Default")
      (node (ref "U3") (pin "5") (pinfunction "DO_5") (pintype "unspecified"))
      (node (ref "U4") (pin "6") (pinfunction "DIN_6") (pintype "unspecified"))
    )
    (net (code "71") (name "Net-(U4-DO)") (class "Default")
      (node (ref "U4") (pin "5") (pinfunction "DO_5") (pintype "unspecified"))
      (node (ref "U5") (pin "6") (pinfunction "DIN_6") (pintype "unspecified"))
    )
    (net (code "72") (name "RX") (class "Default")
      (node (ref "H7") (pin "4") (pinfunction "4_4") (pintype "unspecified"))
      (node (ref "U2") (pin "34") (pinfunction "RXD0_34") (pintype "unspecified"))
    )
    (net (code "73") (name "TX") (class "Default")
      (node (ref "H7") (pin "3") (pinfunction "3_3") (pintype "unspecified"))
      (node (ref "U2") (pin "35") (pinfunction "TXD0_35") (pintype "unspecified"))
    )
    (net (code "74") (name "VCC") (class "Default")
      (node (ref "C1") (pin "1") (pinfunction "1_1") (pintype "unspecified"))
      (node (ref "C4") (pin "2") (pinfunction "2_2") (pintype "input"))
      (node (ref "C5") (pin "1") (pinfunction "1_1") (pintype "unspecified"))
      (node (ref "H5") (pin "4") (pinfunction "4_4") (pintype "unspecified"))
      (node (ref "H6") (pin "4") (pinfunction "4_4") (pintype "unspecified"))
      (node (ref "H7") (pin "1") (pinfunction "1_1") (pintype "unspecified"))
      (node (ref "R1") (pin "2") (pinfunction "2_2") (pintype "unspecified"))
      (node (ref "R3") (pin "2") (pinfunction "2_2") (pintype "unspecified"))
      (node (ref "U1") (pin "2") (pinfunction "VOUT_2") (pintype "unspecified"))
      (node (ref "U2") (pin "2") (pinfunction "VDD33_2") (pintype "unspecified"))
      (node (ref "U6") (pin "3") (pinfunction "VDD_3") (pintype "unspecified"))
    )
    (net (code "75") (name "unconnected-(LED22-DOUT-Pad2)") (class "Default")
      (node (ref "LED22") (pin "2") (pinfunction "DOUT_2") (pintype "unspecified+no_connect"))
    )
    (net (code "76") (name "unconnected-(RST-NO-PadNO2)") (class "Default")
      (node (ref "RST") (pin "NO2") (pinfunction "NO_NO2") (pintype "unspecified"))
    )
    (net (code "77") (name "unconnected-(U2-CLK-Pad20)") (class "Default")
      (node (ref "U2") (pin "20") (pinfunction "CLK_20") (pintype "unspecified"))
    )
    (net (code "78") (name "unconnected-(U2-CMD-Pad19)") (class "Default")
      (node (ref "U2") (pin "19") (pinfunction "CMD_19") (pintype "unspecified"))
    )
    (net (code "79") (name "unconnected-(U2-IO4-Pad26)") (class "Default")
      (node (ref "U2") (pin "26") (pinfunction "IO4_26") (pintype "unspecified"))
    )
    (net (code "80") (name "unconnected-(U2-IO5-Pad29)") (class "Default")
      (node (ref "U2") (pin "29") (pinfunction "IO5_29") (pintype "unspecified"))
    )
    (net (code "81") (name "unconnected-(U2-IO13-Pad16)") (class "Default")
      (node (ref "U2") (pin "16") (pinfunction "IO13_16") (pintype "unspecified"))
    )
    (net (code "82") (name "unconnected-(U2-IO18-Pad30)") (class "Default")
      (node (ref "U2") (pin "30") (pinfunction "IO18_30") (pintype "unspecified"))
    )
    (net (code "83") (name "unconnected-(U2-IO19-Pad31)") (class "Default")
      (node (ref "U2") (pin "31") (pinfunction "IO19_31") (pintype "unspecified"))
    )
    (net (code "84") (name "unconnected-(U2-IO21-Pad33)") (class "Default")
      (node (ref "U2") (pin "33") (pinfunction "IO21_33") (pintype "unspecified"))
    )
    (net (code "85") (name "unconnected-(U2-IO22-Pad36)") (class "Default")
      (node (ref "U2") (pin "36") (pinfunction "IO22_36") (pintype "unspecified"))
    )
    (net (code "86") (name "unconnected-(U2-IO23-Pad37)") (class "Default")
      (node (ref "U2") (pin "37") (pinfunction "IO23_37") (pintype "unspecified"))
    )
    (net (code "87") (name "unconnected-(U2-IO26-Pad11)") (class "Default")
      (node (ref "U2") (pin "11") (pinfunction "IO26_11") (pintype "unspecified"))
    )
    (net (code "88") (name "unconnected-(U2-NC-Pad27)") (class "Default")
      (node (ref "U2") (pin "27") (pinfunction "NC_27") (pintype "unspecified"))
    )
    (net (code "89") (name "unconnected-(U2-NC-Pad28)") (class "Default")
      (node (ref "U2") (pin "28") (pinfunction "NC_28") (pintype "unspecified"))
    )
    (net (code "90") (name "unconnected-(U2-NC-Pad32)") (class "Default")
      (node (ref "U2") (pin "32") (pinfunction "NC_32") (pintype "unspecified"))
    )
    (net (code "91") (name "unconnected-(U2-SD0-Pad21)") (class "Default")
      (node (ref "U2") (pin "21") (pinfunction "SD0_21") (pintype "unspecified"))
    )
    (net (code "92") (name "unconnected-(U2-SD1-Pad22)") (class "Default")
      (node (ref "U2") (pin "22") (pinfunction "SD1_22") (pintype "unspecified"))
    )
    (net (code "93") (name "unconnected-(U2-SD2-Pad17)") (class "Default")
      (node (ref "U2") (pin "17") (pinfunction "SD2_17") (pintype "unspecified"))
    )
    (net (code "94") (name "unconnected-(U2-SD3-Pad18)") (class "Default")
      (node (ref "U2") (pin "18") (pinfunction "SD3_18") (pintype "unspecified"))
    )
    (net (code "95") (name "unconnected-(U2-SENSOR_VN-Pad5)") (class "Default")
      (node (ref "U2") (pin "5") (pinfunction "SENSOR_VN_5") (pintype "unspecified"))
    )
    (net (code "96") (name "unconnected-(U2-SENSOR_VP-Pad4)") (class "Default")
      (node (ref "U2") (pin "4") (pinfunction "SENSOR_VP_4") (pintype "unspecified"))
    )
    (net (code "97") (name "unconnected-(U3-NC-Pad7)") (class "Default")
      (node (ref "U3") (pin "7") (pinfunction "NC_7") (pintype "unspecified"))
    )
    (net (code "98") (name "unconnected-(U4-NC-Pad7)") (class "Default")
      (node (ref "U4") (pin "7") (pinfunction "NC_7") (pintype "unspecified"))
    )
    (net (code "99") (name "unconnected-(U5-DO-Pad5)") (class "Default")
      (node (ref "U5") (pin "5") (pinfunction "DO_5") (pintype "unspecified"))
    )
    (net (code "100") (name "unconnected-(U5-NC-Pad7)") (class "Default")
      (node (ref "U5") (pin "7") (pinfunction "NC_7") (pintype "unspecified"))
    )
    (net (code "101") (name "unconnected-(U5-OUTB-Pad3)") (class "Default")
      (node (ref "U5") (pin "3") (pinfunction "OUTB_3") (pintype "unspecified"))
    )
    (net (code "102") (name "unconnected-(U5-OUTG-Pad2)") (class "Default")
      (node (ref "U5") (pin "2") (pinfunction "OUTG_2") (pintype "unspecified"))
    )
  )
)
